# TDT_CableTester.net
KiCad netlist of a schematic drawn in EAGLE
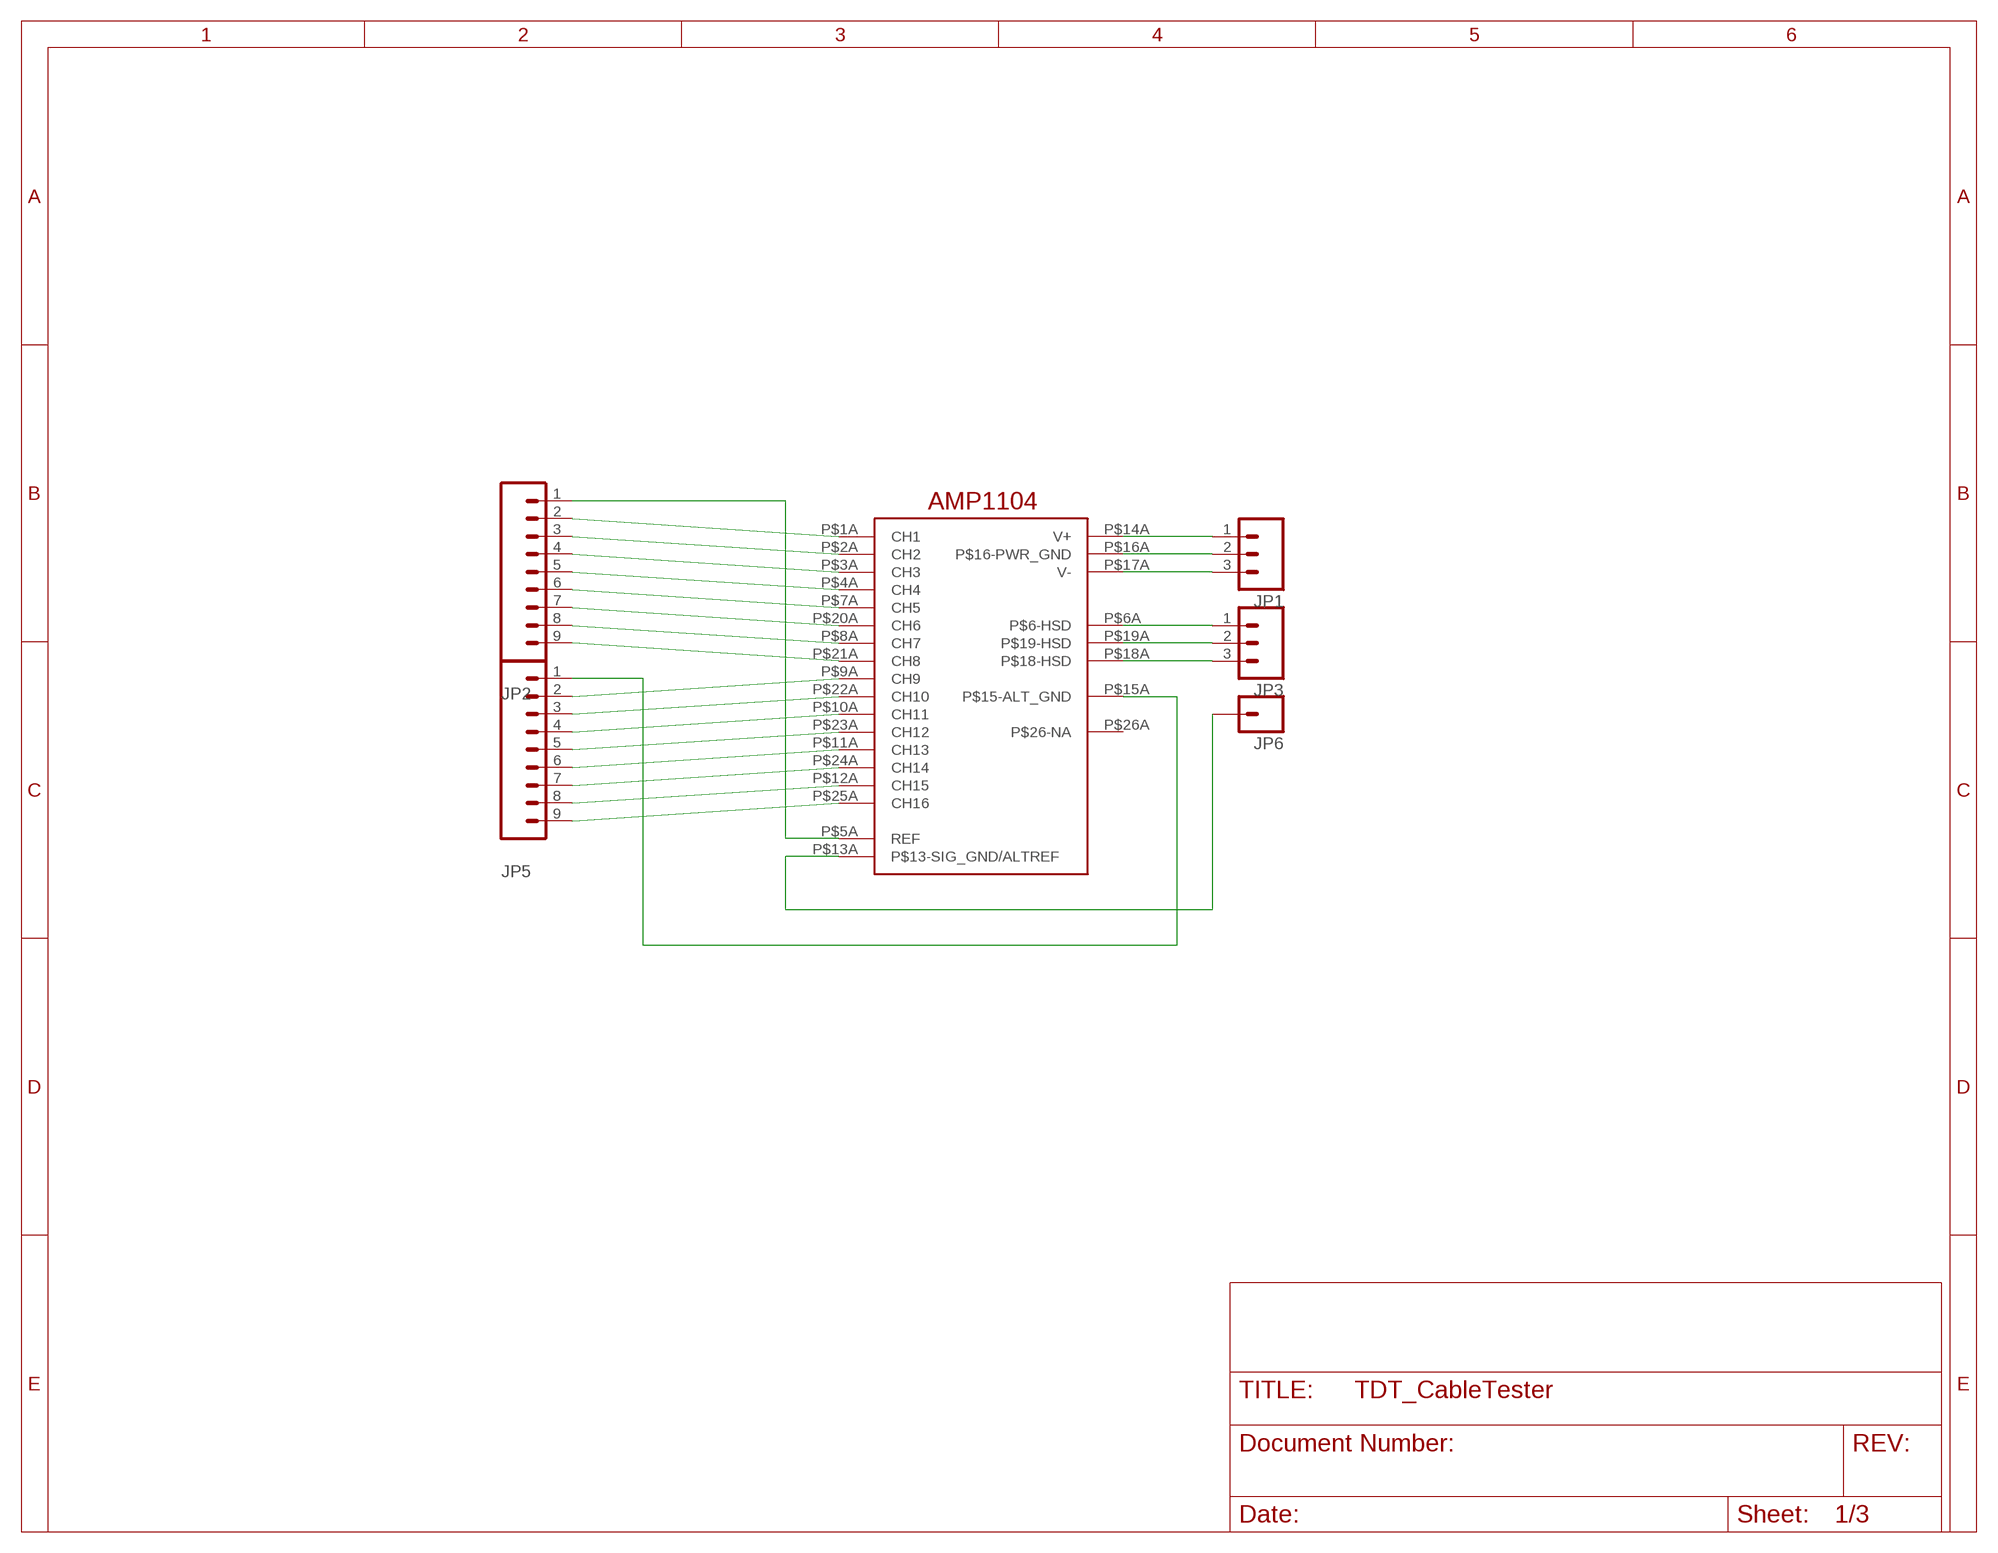
[diagram p0: schematic, sheet 1]

(export (version "E")
  (design (tool "Eeschema 10.0.6"))
  (components
    (comp (ref "JP1")
      (value "M03PTH")
      (footprint "eagle-import:1X03")
      (libsource (lib "eagle-import") (part "M03PTH"))
    )
    (comp (ref "JP2")
      (value "M09")
      (footprint "eagle-import:1X09")
      (libsource (lib "eagle-import") (part "M09"))
    )
    (comp (ref "JP3")
      (value "M03PTH")
      (footprint "eagle-import:1X03")
      (libsource (lib "eagle-import") (part "M03PTH"))
    )
    (comp (ref "JP5")
      (value "M09")
      (footprint "eagle-import:1X09")
      (libsource (lib "eagle-import") (part "M09"))
    )
    (comp (ref "JP6")
      (value "M01PTH")
      (footprint "eagle-import:1X01")
      (libsource (lib "eagle-import") (part "M01PTH"))
    )
    (comp (ref "U$3")
      (value "AMP1104")
      (footprint "eagle-import:AMP1104")
      (libsource (lib "eagle-import") (part "AMP1104"))
    )
  )
  (nets
    (net (code "1") (name "Net-(U$3-CH1)") (class "Default")
      (node (ref "JP2") (pin "2") (pinfunction "2_2") (pintype "passive"))
      (node (ref "U$3") (pin "P$1A") (pinfunction "CH1_P$1A") (pintype "bidirectional"))
    )
    (net (code "2") (name "Net-(U$3-CH2)") (class "Default")
      (node (ref "JP2") (pin "3") (pinfunction "3_3") (pintype "passive"))
      (node (ref "U$3") (pin "P$2A") (pinfunction "CH2_P$2A") (pintype "bidirectional"))
    )
    (net (code "3") (name "Net-(U$3-CH3)") (class "Default")
      (node (ref "JP2") (pin "4") (pinfunction "4_4") (pintype "passive"))
      (node (ref "U$3") (pin "P$3A") (pinfunction "CH3_P$3A") (pintype "bidirectional"))
    )
    (net (code "4") (name "Net-(U$3-CH4)") (class "Default")
      (node (ref "JP2") (pin "5") (pinfunction "5_5") (pintype "passive"))
      (node (ref "U$3") (pin "P$4A") (pinfunction "CH4_P$4A") (pintype "bidirectional"))
    )
    (net (code "5") (name "Net-(U$3-CH5)") (class "Default")
      (node (ref "JP2") (pin "6") (pinfunction "6_6") (pintype "passive"))
      (node (ref "U$3") (pin "P$7A") (pinfunction "CH5_P$7A") (pintype "bidirectional"))
    )
    (net (code "6") (name "Net-(U$3-CH6)") (class "Default")
      (node (ref "JP2") (pin "7") (pinfunction "7_7") (pintype "passive"))
      (node (ref "U$3") (pin "P$20A") (pinfunction "CH6_P$20A") (pintype "bidirectional"))
    )
    (net (code "7") (name "Net-(U$3-CH7)") (class "Default")
      (node (ref "JP2") (pin "8") (pinfunction "8_8") (pintype "passive"))
      (node (ref "U$3") (pin "P$8A") (pinfunction "CH7_P$8A") (pintype "bidirectional"))
    )
    (net (code "8") (name "Net-(U$3-CH8)") (class "Default")
      (node (ref "JP2") (pin "9") (pinfunction "9_9") (pintype "passive"))
      (node (ref "U$3") (pin "P$21A") (pinfunction "CH8_P$21A") (pintype "bidirectional"))
    )
    (net (code "9") (name "Net-(U$3-CH9)") (class "Default")
      (node (ref "JP5") (pin "2") (pinfunction "2_2") (pintype "passive"))
      (node (ref "U$3") (pin "P$9A") (pinfunction "CH9_P$9A") (pintype "bidirectional"))
    )
    (net (code "10") (name "Net-(U$3-CH10)") (class "Default")
      (node (ref "JP5") (pin "3") (pinfunction "3_3") (pintype "passive"))
      (node (ref "U$3") (pin "P$22A") (pinfunction "CH10_P$22A") (pintype "bidirectional"))
    )
    (net (code "11") (name "Net-(U$3-CH11)") (class "Default")
      (node (ref "JP5") (pin "4") (pinfunction "4_4") (pintype "passive"))
      (node (ref "U$3") (pin "P$10A") (pinfunction "CH11_P$10A") (pintype "bidirectional"))
    )
    (net (code "12") (name "Net-(U$3-CH12)") (class "Default")
      (node (ref "JP5") (pin "5") (pinfunction "5_5") (pintype "passive"))
      (node (ref "U$3") (pin "P$23A") (pinfunction "CH12_P$23A") (pintype "bidirectional"))
    )
    (net (code "13") (name "Net-(U$3-CH13)") (class "Default")
      (node (ref "JP5") (pin "6") (pinfunction "6_6") (pintype "passive"))
      (node (ref "U$3") (pin "P$11A") (pinfunction "CH13_P$11A") (pintype "bidirectional"))
    )
    (net (code "14") (name "Net-(U$3-CH14)") (class "Default")
      (node (ref "JP5") (pin "7") (pinfunction "7_7") (pintype "passive"))
      (node (ref "U$3") (pin "P$24A") (pinfunction "CH14_P$24A") (pintype "bidirectional"))
    )
    (net (code "15") (name "Net-(U$3-CH15)") (class "Default")
      (node (ref "JP5") (pin "8") (pinfunction "8_8") (pintype "passive"))
      (node (ref "U$3") (pin "P$12A") (pinfunction "CH15_P$12A") (pintype "bidirectional"))
    )
    (net (code "16") (name "Net-(U$3-CH16)") (class "Default")
      (node (ref "JP5") (pin "9") (pinfunction "9_9") (pintype "passive"))
      (node (ref "U$3") (pin "P$25A") (pinfunction "CH16_P$25A") (pintype "bidirectional"))
    )
    (net (code "17") (name "Net-(U$3-P$6-HSD)") (class "Default")
      (node (ref "JP3") (pin "1") (pinfunction "1_1") (pintype "passive"))
      (node (ref "U$3") (pin "P$6A") (pinfunction "P$6-HSD_P$6A") (pintype "bidirectional"))
    )
    (net (code "18") (name "Net-(U$3-P$13-SIG_GND{slash}ALTREF)") (class "Default")
      (node (ref "JP6") (pin "1") (pinfunction "1_1") (pintype "passive"))
      (node (ref "U$3") (pin "P$13A") (pinfunction "P$13-SIG_GND/ALTREF_P$13A") (pintype "bidirectional"))
    )
    (net (code "19") (name "Net-(U$3-P$15-ALT_GND)") (class "Default")
      (node (ref "JP5") (pin "1") (pinfunction "1_1") (pintype "passive"))
      (node (ref "U$3") (pin "P$15A") (pinfunction "P$15-ALT_GND_P$15A") (pintype "bidirectional"))
    )
    (net (code "20") (name "Net-(U$3-P$16-PWR_GND)") (class "Default")
      (node (ref "JP1") (pin "2") (pinfunction "2_2") (pintype "passive"))
      (node (ref "U$3") (pin "P$16A") (pinfunction "P$16-PWR_GND_P$16A") (pintype "bidirectional"))
    )
    (net (code "21") (name "Net-(U$3-P$18-HSD)") (class "Default")
      (node (ref "JP3") (pin "3") (pinfunction "3_3") (pintype "passive"))
      (node (ref "U$3") (pin "P$18A") (pinfunction "P$18-HSD_P$18A") (pintype "bidirectional"))
    )
    (net (code "22") (name "Net-(U$3-P$19-HSD)") (class "Default")
      (node (ref "JP3") (pin "2") (pinfunction "2_2") (pintype "passive"))
      (node (ref "U$3") (pin "P$19A") (pinfunction "P$19-HSD_P$19A") (pintype "bidirectional"))
    )
    (net (code "23") (name "Net-(U$3-REF)") (class "Default")
      (node (ref "JP2") (pin "1") (pinfunction "1_1") (pintype "passive"))
      (node (ref "U$3") (pin "P$5A") (pinfunction "REF_P$5A") (pintype "bidirectional"))
    )
    (net (code "24") (name "Net-(U$3-V+)") (class "Default")
      (node (ref "JP1") (pin "1") (pinfunction "1_1") (pintype "passive"))
      (node (ref "U$3") (pin "P$14A") (pinfunction "V+_P$14A") (pintype "bidirectional"))
    )
    (net (code "25") (name "Net-(U$3-V-)") (class "Default")
      (node (ref "JP1") (pin "3") (pinfunction "3_3") (pintype "passive"))
      (node (ref "U$3") (pin "P$17A") (pinfunction "V-_P$17A") (pintype "bidirectional"))
    )
    (net (code "26") (name "unconnected-(U$3-P$26-NA-PadP$26A)") (class "Default")
      (node (ref "U$3") (pin "P$26A") (pinfunction "P$26-NA_P$26A") (pintype "bidirectional"))
    )
  )
)
